# RC_Level_Shifter.net
KiCad netlist of a schematic drawn in Altium Designer
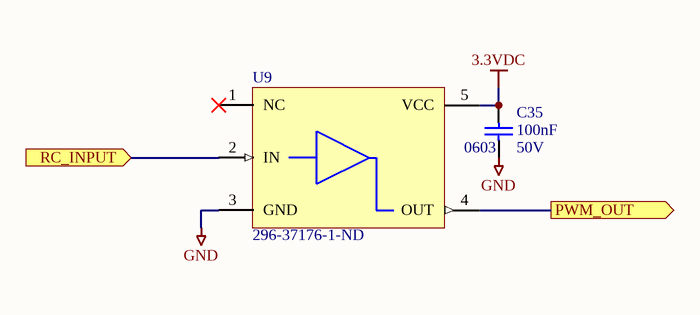
[diagram p0: RC_Level_Shifter.SchDoc]

(export (version "E")
  (design (tool "Eeschema 10.0.6"))
  (components
    (comp (ref "C35")
      (value "100nF")
      (footprint "CAPC1608N(0603\")")
      (description "CAP CER 0.1UF 50V X7R 0603")
      (fields
        (field (name "MANUFACTURER") "Samsung")
        (field (name "MANUFACTURER PART NUMBER") "CL10B104KB8SFNC")
        (field (name "CASE CODE (IMPERIAL)") "0603")
        (field (name "VOLTAGE RATING") "50V")
      )
      (libsource (lib "BLDC_Gimbal_Lib") (part "CL10B104KB8SFNC"))
    )
    (comp (ref "U9")
      (value "SN74LV1T34DBVR")
      (footprint "DBV0005A_M")
      (description "IC BUF NON-INVERT 5.5V SOT23-5")
      (fields
        (field (name "MANUFACTURER") "Texas Instruments")
        (field (name "SUPPLIER PART NUMBER 1") "296-37176-1-ND")
      )
      (libsource (lib "AERO Schematic Library - Buffers & Isolators") (part "SN74LV1T34DBVR"))
    )
  )
  (nets
    (net (code "1") (name "/PWM_OUT") (class "Default")
      (node (ref "U9") (pin "4") (pinfunction "OUT_4") (pintype "output"))
    )
    (net (code "2") (name "/RC_INPUT") (class "Default")
      (node (ref "U9") (pin "2") (pinfunction "IN_2") (pintype "input"))
    )
    (net (code "3") (name "3.3VDC") (class "Default")
      (node (ref "C35") (pin "2") (pinfunction "2_2") (pintype "passive"))
      (node (ref "U9") (pin "5") (pinfunction "VCC_5") (pintype "power_in"))
    )
    (net (code "4") (name "GND") (class "Default")
      (node (ref "C35") (pin "1") (pinfunction "1_1") (pintype "passive"))
      (node (ref "U9") (pin "3") (pinfunction "GND_3") (pintype "power_in"))
    )
    (net (code "5") (name "unconnected-(U9-NC-Pad1)") (class "Default")
      (node (ref "U9") (pin "1") (pinfunction "NC_1") (pintype "passive+no_connect"))
    )
  )
)
